# main_board.net
KiCad netlist of a schematic drawn in EAGLE
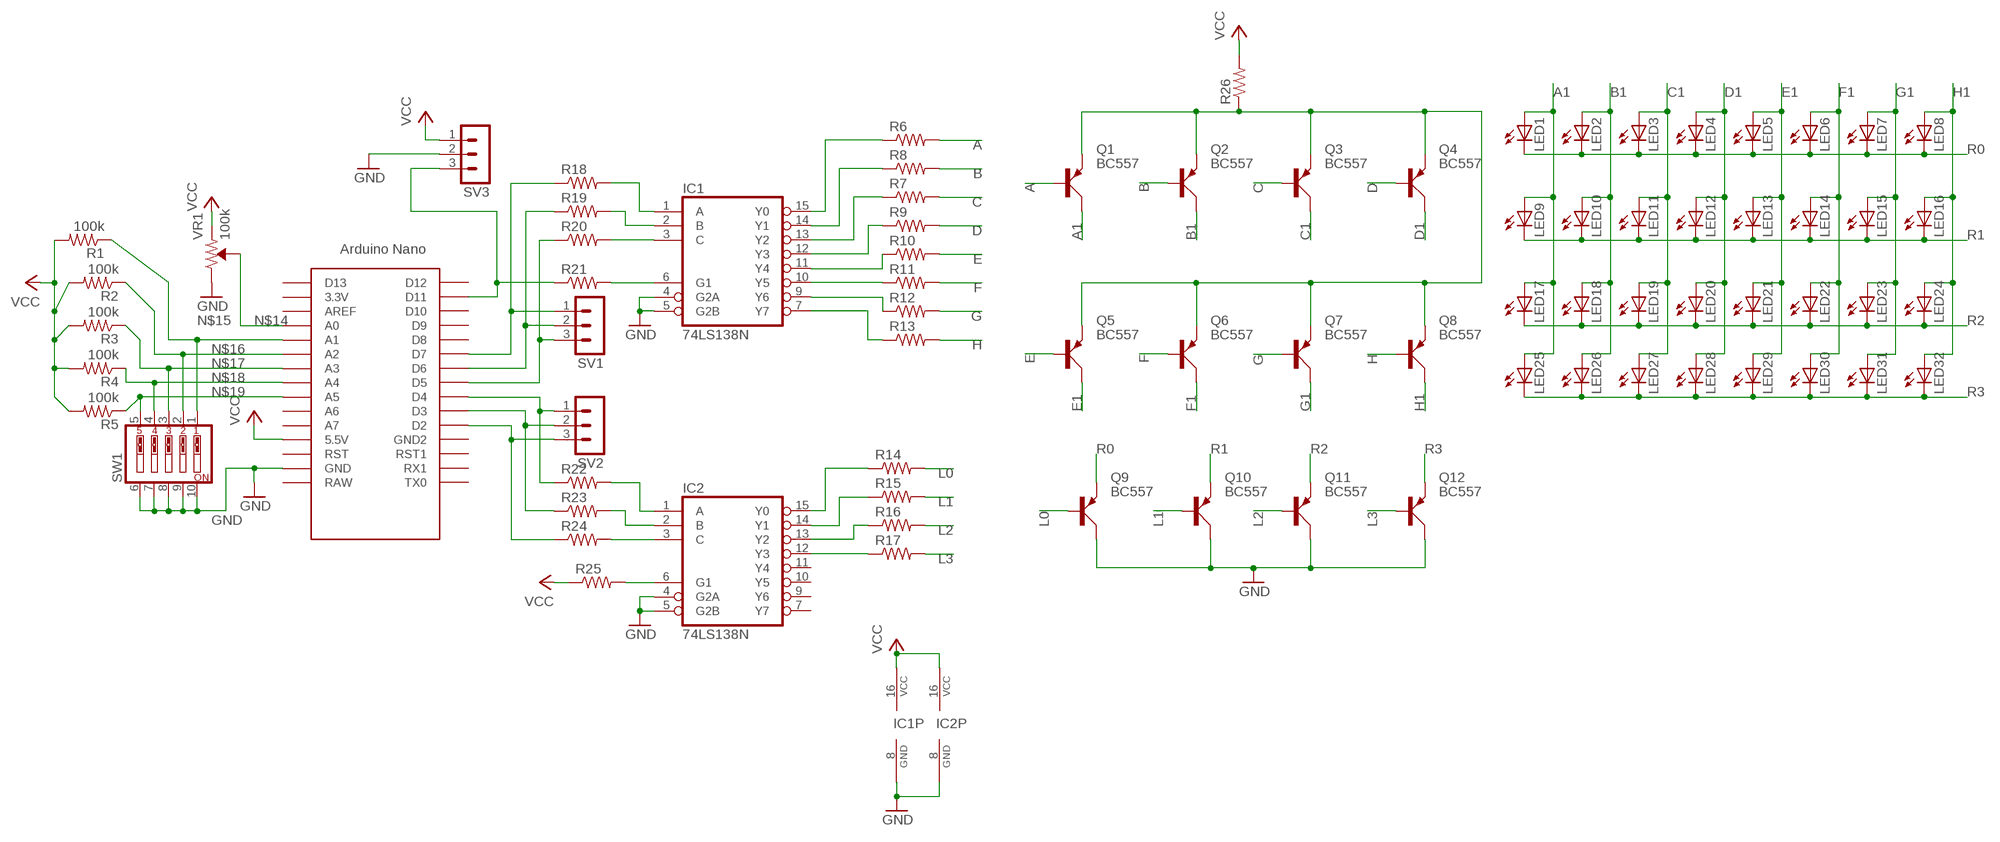
[diagram p0: schematic, sheet 1]

(export (version "E")
  (design (tool "Eeschema 10.0.6"))
  (components
    (comp (ref "ARD1")
      (value "NANO")
      (footprint "eagle-import:NANO")
      (libsource (lib "eagle-import") (part "NANO"))
    )
    (comp (ref "IC1")
      (value "74LS138N")
      (footprint "eagle-import:DIL16")
      (libsource (lib "eagle-import") (part "74138NLS"))
    )
    (comp (ref "IC2")
      (value "74LS138N")
      (footprint "eagle-import:DIL16")
      (libsource (lib "eagle-import") (part "74138NLS"))
    )
    (comp (ref "LED1")
      (value "LED5MM")
      (footprint "eagle-import:LED5MM")
      (libsource (lib "eagle-import") (part "LED5MM"))
    )
    (comp (ref "LED2")
      (value "LED5MM")
      (footprint "eagle-import:LED5MM")
      (libsource (lib "eagle-import") (part "LED5MM"))
    )
    (comp (ref "LED3")
      (value "LED5MM")
      (footprint "eagle-import:LED5MM")
      (libsource (lib "eagle-import") (part "LED5MM"))
    )
    (comp (ref "LED4")
      (value "LED5MM")
      (footprint "eagle-import:LED5MM")
      (libsource (lib "eagle-import") (part "LED5MM"))
    )
    (comp (ref "LED5")
      (value "LED5MM")
      (footprint "eagle-import:LED5MM")
      (libsource (lib "eagle-import") (part "LED5MM"))
    )
    (comp (ref "LED6")
      (value "LED5MM")
      (footprint "eagle-import:LED5MM")
      (libsource (lib "eagle-import") (part "LED5MM"))
    )
    (comp (ref "LED7")
      (value "LED5MM")
      (footprint "eagle-import:LED5MM")
      (libsource (lib "eagle-import") (part "LED5MM"))
    )
    (comp (ref "LED8")
      (value "LED5MM")
      (footprint "eagle-import:LED5MM")
      (libsource (lib "eagle-import") (part "LED5MM"))
    )
    (comp (ref "LED9")
      (value "LED5MM")
      (footprint "eagle-import:LED5MM")
      (libsource (lib "eagle-import") (part "LED5MM"))
    )
    (comp (ref "LED10")
      (value "LED5MM")
      (footprint "eagle-import:LED5MM")
      (libsource (lib "eagle-import") (part "LED5MM"))
    )
    (comp (ref "LED11")
      (value "LED5MM")
      (footprint "eagle-import:LED5MM")
      (libsource (lib "eagle-import") (part "LED5MM"))
    )
    (comp (ref "LED12")
      (value "LED5MM")
      (footprint "eagle-import:LED5MM")
      (libsource (lib "eagle-import") (part "LED5MM"))
    )
    (comp (ref "LED13")
      (value "LED5MM")
      (footprint "eagle-import:LED5MM")
      (libsource (lib "eagle-import") (part "LED5MM"))
    )
    (comp (ref "LED14")
      (value "LED5MM")
      (footprint "eagle-import:LED5MM")
      (libsource (lib "eagle-import") (part "LED5MM"))
    )
    (comp (ref "LED15")
      (value "LED5MM")
      (footprint "eagle-import:LED5MM")
      (libsource (lib "eagle-import") (part "LED5MM"))
    )
    (comp (ref "LED16")
      (value "LED5MM")
      (footprint "eagle-import:LED5MM")
      (libsource (lib "eagle-import") (part "LED5MM"))
    )
    (comp (ref "LED17")
      (value "LED5MM")
      (footprint "eagle-import:LED5MM")
      (libsource (lib "eagle-import") (part "LED5MM"))
    )
    (comp (ref "LED18")
      (value "LED5MM")
      (footprint "eagle-import:LED5MM")
      (libsource (lib "eagle-import") (part "LED5MM"))
    )
    (comp (ref "LED19")
      (value "LED5MM")
      (footprint "eagle-import:LED5MM")
      (libsource (lib "eagle-import") (part "LED5MM"))
    )
    (comp (ref "LED20")
      (value "LED5MM")
      (footprint "eagle-import:LED5MM")
      (libsource (lib "eagle-import") (part "LED5MM"))
    )
    (comp (ref "LED21")
      (value "LED5MM")
      (footprint "eagle-import:LED5MM")
      (libsource (lib "eagle-import") (part "LED5MM"))
    )
    (comp (ref "LED22")
      (value "LED5MM")
      (footprint "eagle-import:LED5MM")
      (libsource (lib "eagle-import") (part "LED5MM"))
    )
    (comp (ref "LED23")
      (value "LED5MM")
      (footprint "eagle-import:LED5MM")
      (libsource (lib "eagle-import") (part "LED5MM"))
    )
    (comp (ref "LED24")
      (value "LED5MM")
      (footprint "eagle-import:LED5MM")
      (libsource (lib "eagle-import") (part "LED5MM"))
    )
    (comp (ref "LED25")
      (value "LED5MM")
      (footprint "eagle-import:LED5MM")
      (libsource (lib "eagle-import") (part "LED5MM"))
    )
    (comp (ref "LED26")
      (value "LED5MM")
      (footprint "eagle-import:LED5MM")
      (libsource (lib "eagle-import") (part "LED5MM"))
    )
    (comp (ref "LED27")
      (value "LED5MM")
      (footprint "eagle-import:LED5MM")
      (libsource (lib "eagle-import") (part "LED5MM"))
    )
    (comp (ref "LED28")
      (value "LED5MM")
      (footprint "eagle-import:LED5MM")
      (libsource (lib "eagle-import") (part "LED5MM"))
    )
    (comp (ref "LED29")
      (value "LED5MM")
      (footprint "eagle-import:LED5MM")
      (libsource (lib "eagle-import") (part "LED5MM"))
    )
    (comp (ref "LED30")
      (value "LED5MM")
      (footprint "eagle-import:LED5MM")
      (libsource (lib "eagle-import") (part "LED5MM"))
    )
    (comp (ref "LED31")
      (value "LED5MM")
      (footprint "eagle-import:LED5MM")
      (libsource (lib "eagle-import") (part "LED5MM"))
    )
    (comp (ref "LED32")
      (value "LED5MM")
      (footprint "eagle-import:LED5MM")
      (libsource (lib "eagle-import") (part "LED5MM"))
    )
    (comp (ref "Q1")
      (value "BC557")
      (footprint "eagle-import:SOT54A")
      (libsource (lib "eagle-import") (part "BC557"))
    )
    (comp (ref "Q2")
      (value "BC557")
      (footprint "eagle-import:SOT54A")
      (libsource (lib "eagle-import") (part "BC557"))
    )
    (comp (ref "Q3")
      (value "BC557")
      (footprint "eagle-import:SOT54A")
      (libsource (lib "eagle-import") (part "BC557"))
    )
    (comp (ref "Q4")
      (value "BC557")
      (footprint "eagle-import:SOT54A")
      (libsource (lib "eagle-import") (part "BC557"))
    )
    (comp (ref "Q5")
      (value "BC557")
      (footprint "eagle-import:SOT54A")
      (libsource (lib "eagle-import") (part "BC557"))
    )
    (comp (ref "Q6")
      (value "BC557")
      (footprint "eagle-import:SOT54A")
      (libsource (lib "eagle-import") (part "BC557"))
    )
    (comp (ref "Q7")
      (value "BC557")
      (footprint "eagle-import:SOT54A")
      (libsource (lib "eagle-import") (part "BC557"))
    )
    (comp (ref "Q8")
      (value "BC557")
      (footprint "eagle-import:SOT54A")
      (libsource (lib "eagle-import") (part "BC557"))
    )
    (comp (ref "Q9")
      (value "BC557")
      (footprint "eagle-import:SOT54A")
      (libsource (lib "eagle-import") (part "BC557"))
    )
    (comp (ref "Q10")
      (value "BC557")
      (footprint "eagle-import:SOT54A")
      (libsource (lib "eagle-import") (part "BC557"))
    )
    (comp (ref "Q11")
      (value "BC557")
      (footprint "eagle-import:SOT54A")
      (libsource (lib "eagle-import") (part "BC557"))
    )
    (comp (ref "Q12")
      (value "BC557")
      (footprint "eagle-import:SOT54A")
      (libsource (lib "eagle-import") (part "BC557"))
    )
    (comp (ref "R1")
      (value "100k")
      (footprint "eagle-import:M0805")
      (libsource (lib "eagle-import") (part "resistor_348_R-US_M0805"))
    )
    (comp (ref "R2")
      (value "100k")
      (footprint "eagle-import:M0805")
      (libsource (lib "eagle-import") (part "resistor_348_R-US_M0805"))
    )
    (comp (ref "R3")
      (value "100k")
      (footprint "eagle-import:M0805")
      (libsource (lib "eagle-import") (part "resistor_348_R-US_M0805"))
    )
    (comp (ref "R4")
      (value "100k")
      (footprint "eagle-import:M0805")
      (libsource (lib "eagle-import") (part "resistor_348_R-US_M0805"))
    )
    (comp (ref "R5")
      (value "100k")
      (footprint "eagle-import:M0805")
      (libsource (lib "eagle-import") (part "resistor_348_R-US_M0805"))
    )
    (comp (ref "R6")
      (value "R-US_R0805")
      (footprint "eagle-import:R0805")
      (libsource (lib "eagle-import") (part "R-US_R0805"))
    )
    (comp (ref "R7")
      (value "R-US_R0805")
      (footprint "eagle-import:R0805")
      (libsource (lib "eagle-import") (part "R-US_R0805"))
    )
    (comp (ref "R8")
      (value "R-US_R0805")
      (footprint "eagle-import:R0805")
      (libsource (lib "eagle-import") (part "R-US_R0805"))
    )
    (comp (ref "R9")
      (value "R-US_R0805")
      (footprint "eagle-import:R0805")
      (libsource (lib "eagle-import") (part "R-US_R0805"))
    )
    (comp (ref "R10")
      (value "R-US_R0805")
      (footprint "eagle-import:R0805")
      (libsource (lib "eagle-import") (part "R-US_R0805"))
    )
    (comp (ref "R11")
      (value "R-US_R0805")
      (footprint "eagle-import:R0805")
      (libsource (lib "eagle-import") (part "R-US_R0805"))
    )
    (comp (ref "R12")
      (value "R-US_R0805")
      (footprint "eagle-import:R0805")
      (libsource (lib "eagle-import") (part "R-US_R0805"))
    )
    (comp (ref "R13")
      (value "R-US_R0805")
      (footprint "eagle-import:R0805")
      (libsource (lib "eagle-import") (part "R-US_R0805"))
    )
    (comp (ref "R14")
      (value "R-US_R0805")
      (footprint "eagle-import:R0805")
      (libsource (lib "eagle-import") (part "R-US_R0805"))
    )
    (comp (ref "R15")
      (value "R-US_R0805")
      (footprint "eagle-import:R0805")
      (libsource (lib "eagle-import") (part "R-US_R0805"))
    )
    (comp (ref "R16")
      (value "R-US_R0805")
      (footprint "eagle-import:R0805")
      (libsource (lib "eagle-import") (part "R-US_R0805"))
    )
    (comp (ref "R17")
      (value "R-US_R0805")
      (footprint "eagle-import:R0805")
      (libsource (lib "eagle-import") (part "R-US_R0805"))
    )
    (comp (ref "R18")
      (value "R-US_M0805")
      (footprint "eagle-import:M0805")
      (libsource (lib "eagle-import") (part "resistor_348_R-US_M0805"))
    )
    (comp (ref "R19")
      (value "R-US_M0805")
      (footprint "eagle-import:M0805")
      (libsource (lib "eagle-import") (part "resistor_348_R-US_M0805"))
    )
    (comp (ref "R20")
      (value "R-US_M0805")
      (footprint "eagle-import:M0805")
      (libsource (lib "eagle-import") (part "resistor_348_R-US_M0805"))
    )
    (comp (ref "R21")
      (value "R-US_M0805")
      (footprint "eagle-import:M0805")
      (libsource (lib "eagle-import") (part "resistor_348_R-US_M0805"))
    )
    (comp (ref "R22")
      (value "R-US_M0805")
      (footprint "eagle-import:M0805")
      (libsource (lib "eagle-import") (part "resistor_348_R-US_M0805"))
    )
    (comp (ref "R23")
      (value "R-US_M0805")
      (footprint "eagle-import:M0805")
      (libsource (lib "eagle-import") (part "resistor_348_R-US_M0805"))
    )
    (comp (ref "R24")
      (value "R-US_M0805")
      (footprint "eagle-import:M0805")
      (libsource (lib "eagle-import") (part "resistor_348_R-US_M0805"))
    )
    (comp (ref "R25")
      (value "R-US_M0805")
      (footprint "eagle-import:M0805")
      (libsource (lib "eagle-import") (part "resistor_348_R-US_M0805"))
    )
    (comp (ref "R26")
      (value "R-US_R0805")
      (footprint "eagle-import:R0805")
      (libsource (lib "eagle-import") (part "R-US_R0805"))
    )
    (comp (ref "SV1")
      (value "MA03-1")
      (footprint "eagle-import:MA03-1")
      (libsource (lib "eagle-import") (part "MA03-1"))
    )
    (comp (ref "SV2")
      (value "MA03-1")
      (footprint "eagle-import:MA03-1")
      (libsource (lib "eagle-import") (part "MA03-1"))
    )
    (comp (ref "SV3")
      (value "MA03-1")
      (footprint "eagle-import:MA03-1")
      (libsource (lib "eagle-import") (part "MA03-1"))
    )
    (comp (ref "SW1")
      (value "SW_DIP-5")
      (footprint "eagle-import:EDG-05")
      (libsource (lib "eagle-import") (part "SW_DIP-5"))
    )
    (comp (ref "VR1")
      (value "100k")
      (footprint "eagle-import:TRIMPOT-PTH-3386U")
      (libsource (lib "eagle-import") (part "TRIMPOT-PTH-10MM-KNOB-1/2W-10%"))
    )
  )
  (nets
    (net (code "1") (name "/A") (class "Default")
      (node (ref "Q1") (pin "B") (pinfunction "B_B") (pintype "passive"))
      (node (ref "R6") (pin "2") (pinfunction "2_2") (pintype "passive"))
    )
    (net (code "2") (name "/A1") (class "Default")
      (node (ref "LED1") (pin "A") (pinfunction "A_A") (pintype "passive"))
      (node (ref "LED17") (pin "A") (pinfunction "A_A") (pintype "passive"))
      (node (ref "LED25") (pin "A") (pinfunction "A_A") (pintype "passive"))
      (node (ref "LED9") (pin "A") (pinfunction "A_A") (pintype "passive"))
      (node (ref "Q1") (pin "C") (pinfunction "C_C") (pintype "passive"))
    )
    (net (code "3") (name "/B") (class "Default")
      (node (ref "Q2") (pin "B") (pinfunction "B_B") (pintype "passive"))
      (node (ref "R8") (pin "2") (pinfunction "2_2") (pintype "passive"))
    )
    (net (code "4") (name "/B1") (class "Default")
      (node (ref "LED10") (pin "A") (pinfunction "A_A") (pintype "passive"))
      (node (ref "LED18") (pin "A") (pinfunction "A_A") (pintype "passive"))
      (node (ref "LED2") (pin "A") (pinfunction "A_A") (pintype "passive"))
      (node (ref "LED26") (pin "A") (pinfunction "A_A") (pintype "passive"))
      (node (ref "Q2") (pin "C") (pinfunction "C_C") (pintype "passive"))
    )
    (net (code "5") (name "/C") (class "Default")
      (node (ref "Q3") (pin "B") (pinfunction "B_B") (pintype "passive"))
      (node (ref "R7") (pin "2") (pinfunction "2_2") (pintype "passive"))
    )
    (net (code "6") (name "/C1") (class "Default")
      (node (ref "LED11") (pin "A") (pinfunction "A_A") (pintype "passive"))
      (node (ref "LED19") (pin "A") (pinfunction "A_A") (pintype "passive"))
      (node (ref "LED27") (pin "A") (pinfunction "A_A") (pintype "passive"))
      (node (ref "LED3") (pin "A") (pinfunction "A_A") (pintype "passive"))
      (node (ref "Q3") (pin "C") (pinfunction "C_C") (pintype "passive"))
    )
    (net (code "7") (name "/D") (class "Default")
      (node (ref "Q4") (pin "B") (pinfunction "B_B") (pintype "passive"))
      (node (ref "R9") (pin "2") (pinfunction "2_2") (pintype "passive"))
    )
    (net (code "8") (name "/D1") (class "Default")
      (node (ref "LED12") (pin "A") (pinfunction "A_A") (pintype "passive"))
      (node (ref "LED20") (pin "A") (pinfunction "A_A") (pintype "passive"))
      (node (ref "LED28") (pin "A") (pinfunction "A_A") (pintype "passive"))
      (node (ref "LED4") (pin "A") (pinfunction "A_A") (pintype "passive"))
      (node (ref "Q4") (pin "C") (pinfunction "C_C") (pintype "passive"))
    )
    (net (code "9") (name "/E") (class "Default")
      (node (ref "Q5") (pin "B") (pinfunction "B_B") (pintype "passive"))
      (node (ref "R10") (pin "2") (pinfunction "2_2") (pintype "passive"))
    )
    (net (code "10") (name "/E1") (class "Default")
      (node (ref "LED13") (pin "A") (pinfunction "A_A") (pintype "passive"))
      (node (ref "LED21") (pin "A") (pinfunction "A_A") (pintype "passive"))
      (node (ref "LED29") (pin "A") (pinfunction "A_A") (pintype "passive"))
      (node (ref "LED5") (pin "A") (pinfunction "A_A") (pintype "passive"))
      (node (ref "Q5") (pin "C") (pinfunction "C_C") (pintype "passive"))
    )
    (net (code "11") (name "/F") (class "Default")
      (node (ref "Q6") (pin "B") (pinfunction "B_B") (pintype "passive"))
      (node (ref "R11") (pin "2") (pinfunction "2_2") (pintype "passive"))
    )
    (net (code "12") (name "/F1") (class "Default")
      (node (ref "LED14") (pin "A") (pinfunction "A_A") (pintype "passive"))
      (node (ref "LED22") (pin "A") (pinfunction "A_A") (pintype "passive"))
      (node (ref "LED30") (pin "A") (pinfunction "A_A") (pintype "passive"))
      (node (ref "LED6") (pin "A") (pinfunction "A_A") (pintype "passive"))
      (node (ref "Q6") (pin "C") (pinfunction "C_C") (pintype "passive"))
    )
    (net (code "13") (name "/G") (class "Default")
      (node (ref "Q7") (pin "B") (pinfunction "B_B") (pintype "passive"))
      (node (ref "R12") (pin "2") (pinfunction "2_2") (pintype "passive"))
    )
    (net (code "14") (name "/G1") (class "Default")
      (node (ref "LED15") (pin "A") (pinfunction "A_A") (pintype "passive"))
      (node (ref "LED23") (pin "A") (pinfunction "A_A") (pintype "passive"))
      (node (ref "LED31") (pin "A") (pinfunction "A_A") (pintype "passive"))
      (node (ref "LED7") (pin "A") (pinfunction "A_A") (pintype "passive"))
      (node (ref "Q7") (pin "C") (pinfunction "C_C") (pintype "passive"))
    )
    (net (code "15") (name "/H") (class "Default")
      (node (ref "Q8") (pin "B") (pinfunction "B_B") (pintype "passive"))
      (node (ref "R13") (pin "2") (pinfunction "2_2") (pintype "passive"))
    )
    (net (code "16") (name "/H1") (class "Default")
      (node (ref "LED16") (pin "A") (pinfunction "A_A") (pintype "passive"))
      (node (ref "LED24") (pin "A") (pinfunction "A_A") (pintype "passive"))
      (node (ref "LED32") (pin "A") (pinfunction "A_A") (pintype "passive"))
      (node (ref "LED8") (pin "A") (pinfunction "A_A") (pintype "passive"))
      (node (ref "Q8") (pin "C") (pinfunction "C_C") (pintype "passive"))
    )
    (net (code "17") (name "/L0") (class "Default")
      (node (ref "Q9") (pin "B") (pinfunction "B_B") (pintype "passive"))
      (node (ref "R14") (pin "2") (pinfunction "2_2") (pintype "passive"))
    )
    (net (code "18") (name "/L1") (class "Default")
      (node (ref "Q10") (pin "B") (pinfunction "B_B") (pintype "passive"))
      (node (ref "R15") (pin "2") (pinfunction "2_2") (pintype "passive"))
    )
    (net (code "19") (name "/L2") (class "Default")
      (node (ref "Q11") (pin "B") (pinfunction "B_B") (pintype "passive"))
      (node (ref "R16") (pin "2") (pinfunction "2_2") (pintype "passive"))
    )
    (net (code "20") (name "/L3") (class "Default")
      (node (ref "Q12") (pin "B") (pinfunction "B_B") (pintype "passive"))
      (node (ref "R17") (pin "2") (pinfunction "2_2") (pintype "passive"))
    )
    (net (code "21") (name "/N$14") (class "Default")
      (node (ref "ARD1") (pin "A0") (pinfunction "A0_A0") (pintype "bidirectional"))
      (node (ref "VR1") (pin "2") (pinfunction "WIPER_2") (pintype "passive"))
    )
    (net (code "22") (name "/N$15") (class "Default")
      (node (ref "ARD1") (pin "A1") (pinfunction "A1_A1") (pintype "bidirectional"))
      (node (ref "R1") (pin "1") (pinfunction "1_1") (pintype "passive"))
      (node (ref "SW1") (pin "1") (pinfunction "1_1") (pintype "passive"))
    )
    (net (code "23") (name "/N$16") (class "Default")
      (node (ref "ARD1") (pin "A2") (pinfunction "A2_A2") (pintype "bidirectional"))
      (node (ref "R2") (pin "1") (pinfunction "1_1") (pintype "passive"))
      (node (ref "SW1") (pin "2") (pinfunction "2_2") (pintype "passive"))
    )
    (net (code "24") (name "/N$17") (class "Default")
      (node (ref "ARD1") (pin "A3") (pinfunction "A3_A3") (pintype "bidirectional"))
      (node (ref "R3") (pin "1") (pinfunction "1_1") (pintype "passive"))
      (node (ref "SW1") (pin "3") (pinfunction "3_3") (pintype "passive"))
    )
    (net (code "25") (name "/N$18") (class "Default")
      (node (ref "ARD1") (pin "A4") (pinfunction "A4_A4") (pintype "bidirectional"))
      (node (ref "R4") (pin "1") (pinfunction "1_1") (pintype "passive"))
      (node (ref "SW1") (pin "4") (pinfunction "4_4") (pintype "passive"))
    )
    (net (code "26") (name "/N$19") (class "Default")
      (node (ref "ARD1") (pin "A5") (pinfunction "A5_A5") (pintype "bidirectional"))
      (node (ref "R5") (pin "1") (pinfunction "1_1") (pintype "passive"))
      (node (ref "SW1") (pin "5") (pinfunction "5_5") (pintype "passive"))
    )
    (net (code "27") (name "/R0") (class "Default")
      (node (ref "LED1") (pin "K") (pinfunction "C_K") (pintype "passive"))
      (node (ref "LED2") (pin "K") (pinfunction "C_K") (pintype "passive"))
      (node (ref "LED3") (pin "K") (pinfunction "C_K") (pintype "passive"))
      (node (ref "LED4") (pin "K") (pinfunction "C_K") (pintype "passive"))
      (node (ref "LED5") (pin "K") (pinfunction "C_K") (pintype "passive"))
      (node (ref "LED6") (pin "K") (pinfunction "C_K") (pintype "passive"))
      (node (ref "LED7") (pin "K") (pinfunction "C_K") (pintype "passive"))
      (node (ref "LED8") (pin "K") (pinfunction "C_K") (pintype "passive"))
      (node (ref "Q9") (pin "E") (pinfunction "E_E") (pintype "passive"))
    )
    (net (code "28") (name "/R1") (class "Default")
      (node (ref "LED10") (pin "K") (pinfunction "C_K") (pintype "passive"))
      (node (ref "LED11") (pin "K") (pinfunction "C_K") (pintype "passive"))
      (node (ref "LED12") (pin "K") (pinfunction "C_K") (pintype "passive"))
      (node (ref "LED13") (pin "K") (pinfunction "C_K") (pintype "passive"))
      (node (ref "LED14") (pin "K") (pinfunction "C_K") (pintype "passive"))
      (node (ref "LED15") (pin "K") (pinfunction "C_K") (pintype "passive"))
      (node (ref "LED16") (pin "K") (pinfunction "C_K") (pintype "passive"))
      (node (ref "LED9") (pin "K") (pinfunction "C_K") (pintype "passive"))
      (node (ref "Q10") (pin "E") (pinfunction "E_E") (pintype "passive"))
    )
    (net (code "29") (name "/R2") (class "Default")
      (node (ref "LED17") (pin "K") (pinfunction "C_K") (pintype "passive"))
      (node (ref "LED18") (pin "K") (pinfunction "C_K") (pintype "passive"))
      (node (ref "LED19") (pin "K") (pinfunction "C_K") (pintype "passive"))
      (node (ref "LED20") (pin "K") (pinfunction "C_K") (pintype "passive"))
      (node (ref "LED21") (pin "K") (pinfunction "C_K") (pintype "passive"))
      (node (ref "LED22") (pin "K") (pinfunction "C_K") (pintype "passive"))
      (node (ref "LED23") (pin "K") (pinfunction "C_K") (pintype "passive"))
      (node (ref "LED24") (pin "K") (pinfunction "C_K") (pintype "passive"))
      (node (ref "Q11") (pin "E") (pinfunction "E_E") (pintype "passive"))
    )
    (net (code "30") (name "/R3") (class "Default")
      (node (ref "LED25") (pin "K") (pinfunction "C_K") (pintype "passive"))
      (node (ref "LED26") (pin "K") (pinfunction "C_K") (pintype "passive"))
      (node (ref "LED27") (pin "K") (pinfunction "C_K") (pintype "passive"))
      (node (ref "LED28") (pin "K") (pinfunction "C_K") (pintype "passive"))
      (node (ref "LED29") (pin "K") (pinfunction "C_K") (pintype "passive"))
      (node (ref "LED30") (pin "K") (pinfunction "C_K") (pintype "passive"))
      (node (ref "LED31") (pin "K") (pinfunction "C_K") (pintype "passive"))
      (node (ref "LED32") (pin "K") (pinfunction "C_K") (pintype "passive"))
      (node (ref "Q12") (pin "E") (pinfunction "E_E") (pintype "passive"))
    )
    (net (code "31") (name "GND") (class "Default")
      (node (ref "ARD1") (pin "GND") (pinfunction "GND_GND") (pintype "bidirectional"))
      (node (ref "IC1") (pin "4") (pinfunction "G2A_4") (pintype "input"))
      (node (ref "IC1") (pin "5") (pinfunction "G2B_5") (pintype "input"))
      (node (ref "IC1") (pin "8") (pinfunction "GND_8") (pintype "power_in"))
      (node (ref "IC2") (pin "4") (pinfunction "G2A_4") (pintype "input"))
      (node (ref "IC2") (pin "5") (pinfunction "G2B_5") (pintype "input"))
      (node (ref "IC2") (pin "8") (pinfunction "GND_8") (pintype "power_in"))
      (node (ref "Q10") (pin "C") (pinfunction "C_C") (pintype "passive"))
      (node (ref "Q11") (pin "C") (pinfunction "C_C") (pintype "passive"))
      (node (ref "Q12") (pin "C") (pinfunction "C_C") (pintype "passive"))
      (node (ref "Q9") (pin "C") (pinfunction "C_C") (pintype "passive"))
      (node (ref "SV3") (pin "2") (pinfunction "2_2") (pintype "passive"))
      (node (ref "SW1") (pin "10") (pinfunction "10_10") (pintype "passive"))
      (node (ref "SW1") (pin "6") (pinfunction "6_6") (pintype "passive"))
      (node (ref "SW1") (pin "7") (pinfunction "7_7") (pintype "passive"))
      (node (ref "SW1") (pin "8") (pinfunction "8_8") (pintype "passive"))
      (node (ref "SW1") (pin "9") (pinfunction "9_9") (pintype "passive"))
      (node (ref "VR1") (pin "3") (pinfunction "CW_3") (pintype "passive"))
    )
    (net (code "32") (name "Net-(ARD1-PadD2)") (class "Default")
      (node (ref "ARD1") (pin "D2") (pinfunction "D2_D2") (pintype "bidirectional"))
      (node (ref "R24") (pin "1") (pinfunction "1_1") (pintype "passive"))
      (node (ref "SV2") (pin "3") (pinfunction "3_3") (pintype "passive"))
    )
    (net (code "33") (name "Net-(ARD1-PadD3)") (class "Default")
      (node (ref "ARD1") (pin "D3") (pinfunction "D3_D3") (pintype "bidirectional"))
      (node (ref "R23") (pin "1") (pinfunction "1_1") (pintype "passive"))
      (node (ref "SV2") (pin "2") (pinfunction "2_2") (pintype "passive"))
    )
    (net (code "34") (name "Net-(ARD1-PadD4)") (class "Default")
      (node (ref "ARD1") (pin "D4") (pinfunction "D4_D4") (pintype "bidirectional"))
      (node (ref "R22") (pin "1") (pinfunction "1_1") (pintype "passive"))
      (node (ref "SV2") (pin "1") (pinfunction "1_1") (pintype "passive"))
    )
    (net (code "35") (name "Net-(ARD1-PadD5)") (class "Default")
      (node (ref "ARD1") (pin "D5") (pinfunction "D5_D5") (pintype "bidirectional"))
      (node (ref "R20") (pin "1") (pinfunction "1_1") (pintype "passive"))
      (node (ref "SV1") (pin "3") (pinfunction "3_3") (pintype "passive"))
    )
    (net (code "36") (name "Net-(ARD1-PadD6)") (class "Default")
      (node (ref "ARD1") (pin "D6") (pinfunction "D6_D6") (pintype "bidirectional"))
      (node (ref "R19") (pin "1") (pinfunction "1_1") (pintype "passive"))
      (node (ref "SV1") (pin "2") (pinfunction "2_2") (pintype "passive"))
    )
    (net (code "37") (name "Net-(ARD1-PadD7)") (class "Default")
      (node (ref "ARD1") (pin "D7") (pinfunction "D7_D7") (pintype "bidirectional"))
      (node (ref "R18") (pin "1") (pinfunction "1_1") (pintype "passive"))
      (node (ref "SV1") (pin "1") (pinfunction "1_1") (pintype "passive"))
    )
    (net (code "38") (name "Net-(ARD1-PadD11)") (class "Default")
      (node (ref "ARD1") (pin "D11") (pinfunction "D11_D11") (pintype "bidirectional"))
      (node (ref "R21") (pin "1") (pinfunction "1_1") (pintype "passive"))
      (node (ref "SV3") (pin "3") (pinfunction "3_3") (pintype "passive"))
    )
    (net (code "39") (name "Net-(IC1A-A)") (class "Default")
      (node (ref "IC1") (pin "1") (pinfunction "A_1") (pintype "input"))
      (node (ref "R18") (pin "2") (pinfunction "2_2") (pintype "passive"))
    )
    (net (code "40") (name "Net-(IC1A-B)") (class "Default")
      (node (ref "IC1") (pin "2") (pinfunction "B_2") (pintype "input"))
      (node (ref "R19") (pin "2") (pinfunction "2_2") (pintype "passive"))
    )
    (net (code "41") (name "Net-(IC1A-C)") (class "Default")
      (node (ref "IC1") (pin "3") (pinfunction "C_3") (pintype "input"))
      (node (ref "R20") (pin "2") (pinfunction "2_2") (pintype "passive"))
    )
    (net (code "42") (name "Net-(IC1A-G1)") (class "Default")
      (node (ref "IC1") (pin "6") (pinfunction "G1_6") (pintype "input"))
      (node (ref "R21") (pin "2") (pinfunction "2_2") (pintype "passive"))
    )
    (net (code "43") (name "Net-(IC1A-Y0)") (class "Default")
      (node (ref "IC1") (pin "15") (pinfunction "Y0_15") (pintype "output"))
      (node (ref "R6") (pin "1") (pinfunction "1_1") (pintype "passive"))
    )
    (net (code "44") (name "Net-(IC1A-Y1)") (class "Default")
      (node (ref "IC1") (pin "14") (pinfunction "Y1_14") (pintype "output"))
      (node (ref "R8") (pin "1") (pinfunction "1_1") (pintype "passive"))
    )
    (net (code "45") (name "Net-(IC1A-Y2)") (class "Default")
      (node (ref "IC1") (pin "13") (pinfunction "Y2_13") (pintype "output"))
      (node (ref "R7") (pin "1") (pinfunction "1_1") (pintype "passive"))
    )
    (net (code "46") (name "Net-(IC1A-Y3)") (class "Default")
      (node (ref "IC1") (pin "12") (pinfunction "Y3_12") (pintype "output"))
      (node (ref "R9") (pin "1") (pinfunction "1_1") (pintype "passive"))
    )
    (net (code "47") (name "Net-(IC1A-Y4)") (class "Default")
      (node (ref "IC1") (pin "11") (pinfunction "Y4_11") (pintype "output"))
      (node (ref "R10") (pin "1") (pinfunction "1_1") (pintype "passive"))
    )
    (net (code "48") (name "Net-(IC1A-Y5)") (class "Default")
      (node (ref "IC1") (pin "10") (pinfunction "Y5_10") (pintype "output"))
      (node (ref "R11") (pin "1") (pinfunction "1_1") (pintype "passive"))
    )
    (net (code "49") (name "Net-(IC1A-Y6)") (class "Default")
      (node (ref "IC1") (pin "9") (pinfunction "Y6_9") (pintype "output"))
      (node (ref "R12") (pin "1") (pinfunction "1_1") (pintype "passive"))
    )
    (net (code "50") (name "Net-(IC1A-Y7)") (class "Default")
      (node (ref "IC1") (pin "7") (pinfunction "Y7_7") (pintype "output"))
      (node (ref "R13") (pin "1") (pinfunction "1_1") (pintype "passive"))
    )
    (net (code "51") (name "Net-(IC2A-A)") (class "Default")
      (node (ref "IC2") (pin "1") (pinfunction "A_1") (pintype "input"))
      (node (ref "R22") (pin "2") (pinfunction "2_2") (pintype "passive"))
    )
    (net (code "52") (name "Net-(IC2A-B)") (class "Default")
      (node (ref "IC2") (pin "2") (pinfunction "B_2") (pintype "input"))
      (node (ref "R23") (pin "2") (pinfunction "2_2") (pintype "passive"))
    )
    (net (code "53") (name "Net-(IC2A-C)") (class "Default")
      (node (ref "IC2") (pin "3") (pinfunction "C_3") (pintype "input"))
      (node (ref "R24") (pin "2") (pinfunction "2_2") (pintype "passive"))
    )
    (net (code "54") (name "Net-(IC2A-G1)") (class "Default")
      (node (ref "IC2") (pin "6") (pinfunction "G1_6") (pintype "input"))
      (node (ref "R25") (pin "2") (pinfunction "2_2") (pintype "passive"))
    )
    (net (code "55") (name "Net-(IC2A-Y0)") (class "Default")
      (node (ref "IC2") (pin "15") (pinfunction "Y0_15") (pintype "output"))
      (node (ref "R14") (pin "1") (pinfunction "1_1") (pintype "passive"))
    )
    (net (code "56") (name "Net-(IC2A-Y1)") (class "Default")
      (node (ref "IC2") (pin "14") (pinfunction "Y1_14") (pintype "output"))
      (node (ref "R15") (pin "1") (pinfunction "1_1") (pintype "passive"))
    )
    (net (code "57") (name "Net-(IC2A-Y2)") (class "Default")
      (node (ref "IC2") (pin "13") (pinfunction "Y2_13") (pintype "output"))
      (node (ref "R16") (pin "1") (pinfunction "1_1") (pintype "passive"))
    )
    (net (code "58") (name "Net-(IC2A-Y3)") (class "Default")
      (node (ref "IC2") (pin "12") (pinfunction "Y3_12") (pintype "output"))
      (node (ref "R17") (pin "1") (pinfunction "1_1") (pintype "passive"))
    )
    (net (code "59") (name "Net-(Q1-PadE)") (class "Default")
      (node (ref "Q1") (pin "E") (pinfunction "E_E") (pintype "passive"))
      (node (ref "Q2") (pin "E") (pinfunction "E_E") (pintype "passive"))
      (node (ref "Q3") (pin "E") (pinfunction "E_E") (pintype "passive"))
      (node (ref "Q4") (pin "E") (pinfunction "E_E") (pintype "passive"))
      (node (ref "Q5") (pin "E") (pinfunction "E_E") (pintype "passive"))
      (node (ref "Q6") (pin "E") (pinfunction "E_E") (pintype "passive"))
      (node (ref "Q7") (pin "E") (pinfunction "E_E") (pintype "passive"))
      (node (ref "Q8") (pin "E") (pinfunction "E_E") (pintype "passive"))
      (node (ref "R26") (pin "1") (pinfunction "1_1") (pintype "passive"))
    )
    (net (code "60") (name "VCC") (class "Default")
      (node (ref "ARD1") (pin "5V") (pinfunction "5.5V_5V") (pintype "bidirectional"))
      (node (ref "IC1") (pin "16") (pinfunction "VCC_16") (pintype "power_in"))
      (node (ref "IC2") (pin "16") (pinfunction "VCC_16") (pintype "power_in"))
      (node (ref "R1") (pin "2") (pinfunction "2_2") (pintype "passive"))
      (node (ref "R2") (pin "2") (pinfunction "2_2") (pintype "passive"))
      (node (ref "R25") (pin "1") (pinfunction "1_1") (pintype "passive"))
      (node (ref "R26") (pin "2") (pinfunction "2_2") (pintype "passive"))
      (node (ref "R3") (pin "2") (pinfunction "2_2") (pintype "passive"))
      (node (ref "R4") (pin "2") (pinfunction "2_2") (pintype "passive"))
      (node (ref "R5") (pin "2") (pinfunction "2_2") (pintype "passive"))
      (node (ref "SV3") (pin "1") (pinfunction "1_1") (pintype "passive"))
      (node (ref "VR1") (pin "1") (pinfunction "CCW_1") (pintype "passive"))
    )
    (net (code "61") (name "unconnected-(ARD1-GND2-PadGND1)") (class "Default")
      (node (ref "ARD1") (pin "GND1") (pinfunction "GND2_GND1") (pintype "bidirectional"))
    )
    (net (code "62") (name "unconnected-(ARD1-Pad3.3V)") (class "Default")
      (node (ref "ARD1") (pin "3.3V") (pinfunction "3.3V_3.3V") (pintype "bidirectional"))
    )
    (net (code "63") (name "unconnected-(ARD1-PadA6)") (class "Default")
      (node (ref "ARD1") (pin "A6") (pinfunction "A6_A6") (pintype "bidirectional"))
    )
    (net (code "64") (name "unconnected-(ARD1-PadA7)") (class "Default")
      (node (ref "ARD1") (pin "A7") (pinfunction "A7_A7") (pintype "bidirectional"))
    )
    (net (code "65") (name "unconnected-(ARD1-PadAREF)") (class "Default")
      (node (ref "ARD1") (pin "AREF") (pinfunction "AREF_AREF") (pintype "bidirectional"))
    )
    (net (code "66") (name "unconnected-(ARD1-PadD8)") (class "Default")
      (node (ref "ARD1") (pin "D8") (pinfunction "D8_D8") (pintype "bidirectional"))
    )
    (net (code "67") (name "unconnected-(ARD1-PadD9)") (class "Default")
      (node (ref "ARD1") (pin "D9") (pinfunction "D9_D9") (pintype "bidirectional"))
    )
    (net (code "68") (name "unconnected-(ARD1-PadD10)") (class "Default")
      (node (ref "ARD1") (pin "D10") (pinfunction "D10_D10") (pintype "bidirectional"))
    )
    (net (code "69") (name "unconnected-(ARD1-PadD12)") (class "Default")
      (node (ref "ARD1") (pin "D12") (pinfunction "D12_D12") (pintype "bidirectional"))
    )
    (net (code "70") (name "unconnected-(ARD1-PadD13)") (class "Default")
      (node (ref "ARD1") (pin "D13") (pinfunction "D13_D13") (pintype "bidirectional"))
    )
    (net (code "71") (name "unconnected-(ARD1-PadICSP1)") (class "Default")
      (node (ref "ARD1") (pin "ICSP1") (pinfunction "ICSP1_ICSP1") (pintype "bidirectional"))
    )
    (net (code "72") (name "unconnected-(ARD1-PadICSP2)") (class "Default")
      (node (ref "ARD1") (pin "ICSP2") (pinfunction "ICSP2_ICSP2") (pintype "bidirectional"))
    )
    (net (code "73") (name "unconnected-(ARD1-PadICSP3)") (class "Default")
      (node (ref "ARD1") (pin "ICSP3") (pinfunction "ICSP3_ICSP3") (pintype "bidirectional"))
    )
    (net (code "74") (name "unconnected-(ARD1-PadICSP4)") (class "Default")
      (node (ref "ARD1") (pin "ICSP4") (pinfunction "ICSP4_ICSP4") (pintype "bidirectional"))
    )
    (net (code "75") (name "unconnected-(ARD1-PadICSP5)") (class "Default")
      (node (ref "ARD1") (pin "ICSP5") (pinfunction "ICSP5_ICSP5") (pintype "bidirectional"))
    )
    (net (code "76") (name "unconnected-(ARD1-PadICSP6)") (class "Default")
      (node (ref "ARD1") (pin "ICSP6") (pinfunction "ICSP6_ICSP6") (pintype "bidirectional"))
    )
    (net (code "77") (name "unconnected-(ARD1-PadRAW)") (class "Default")
      (node (ref "ARD1") (pin "RAW") (pinfunction "RAW_RAW") (pintype "bidirectional"))
    )
    (net (code "78") (name "unconnected-(ARD1-PadRST)") (class "Default")
      (node (ref "ARD1") (pin "RST") (pinfunction "RST_RST") (pintype "bidirectional"))
    )
    (net (code "79") (name "unconnected-(ARD1-PadRST1)") (class "Default")
      (node (ref "ARD1") (pin "RST1") (pinfunction "RST1_RST1") (pintype "bidirectional"))
    )
    (net (code "80") (name "unconnected-(ARD1-PadRX1)") (class "Default")
      (node (ref "ARD1") (pin "RX1") (pinfunction "RX1_RX1") (pintype "bidirectional"))
    )
    (net (code "81") (name "unconnected-(ARD1-PadTX0)") (class "Default")
      (node (ref "ARD1") (pin "TX0") (pinfunction "TX0_TX0") (pintype "bidirectional"))
    )
    (net (code "82") (name "unconnected-(IC2A-Y4-Pad11)") (class "Default")
      (node (ref "IC2") (pin "11") (pinfunction "Y4_11") (pintype "output"))
    )
    (net (code "83") (name "unconnected-(IC2A-Y5-Pad10)") (class "Default")
      (node (ref "IC2") (pin "10") (pinfunction "Y5_10") (pintype "output"))
    )
    (net (code "84") (name "unconnected-(IC2A-Y6-Pad9)") (class "Default")
      (node (ref "IC2") (pin "9") (pinfunction "Y6_9") (pintype "output"))
    )
    (net (code "85") (name "unconnected-(IC2A-Y7-Pad7)") (class "Default")
      (node (ref "IC2") (pin "7") (pinfunction "Y7_7") (pintype "output"))
    )
  )
)
